# Memory.net
KiCad netlist of a schematic drawn in Altium Designer
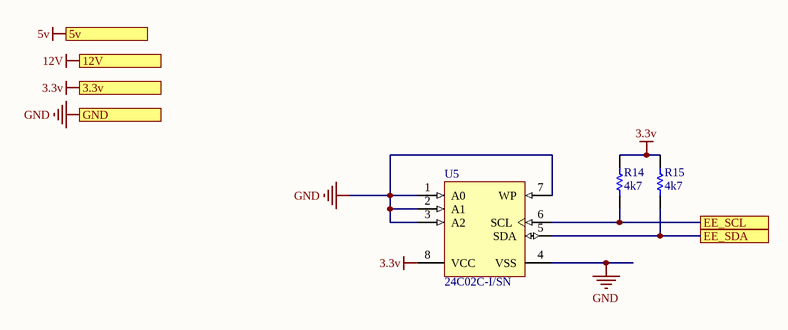
[diagram p0: Memory.SchDoc]

(export (version "E")
  (design (tool "Eeschema 10.0.6"))
  (components
    (comp (ref "R14")
      (value "4k7")
      (footprint "RES 0805 (2012X06L)")
      (description "Resistor")
      (fields (field (name "Comment") "Res1") (field (name "PUBLISHER") "Altium Limited"))
      (libsource (lib "Miscellaneous Devices") (part "Res1"))
    )
    (comp (ref "R15")
      (value "4k7")
      (footprint "RES 0805 optional")
      (description "Resistor")
      (fields (field (name "Comment") "Res1") (field (name "PUBLISHER") "Altium Limited"))
      (libsource (lib "Miscellaneous Devices") (part "Res1"))
    )
    (comp (ref "U5")
      (value "24C02C-I/SN")
      (footprint "SOIC-SN8_L")
      (description "2Kbit, 400kHz, 5V, I2C Serial EEPROM, 8-Pin SOIC 150mil, Industrial Temperature")
      (fields (field (name "PUBLISHER") "Altium Limited"))
      (libsource (lib "Microchip Memory I2C Serial EEPROM") (part "24C02C-I/SN"))
    )
  )
  (nets
    (net (code "1") (name "/EE_SCL") (class "Default")
      (node (ref "R14") (pin "1") (pinfunction "1_1") (pintype "passive"))
      (node (ref "U5") (pin "6") (pinfunction "SCL_6") (pintype "input"))
    )
    (net (code "2") (name "/EE_SDA") (class "Default")
      (node (ref "R15") (pin "1") (pinfunction "1_1") (pintype "passive"))
      (node (ref "U5") (pin "5") (pinfunction "SDA_5") (pintype "bidirectional"))
    )
    (net (code "3") (name "3.3v") (class "Default")
      (node (ref "R14") (pin "2") (pinfunction "2_2") (pintype "passive"))
      (node (ref "R15") (pin "2") (pinfunction "2_2") (pintype "passive"))
      (node (ref "U5") (pin "8") (pinfunction "VCC_8") (pintype "power_in"))
    )
    (net (code "6") (name "GND") (class "Default")
      (node (ref "U5") (pin "1") (pinfunction "A0_1") (pintype "input"))
      (node (ref "U5") (pin "2") (pinfunction "A1_2") (pintype "input"))
      (node (ref "U5") (pin "3") (pinfunction "A2_3") (pintype "input"))
      (node (ref "U5") (pin "4") (pinfunction "VSS_4") (pintype "power_in"))
      (node (ref "U5") (pin "7") (pinfunction "WP_7") (pintype "input"))
    )
  )
)
